# CFA_T_4L.net
KiCad netlist of a schematic drawn in EAGLE
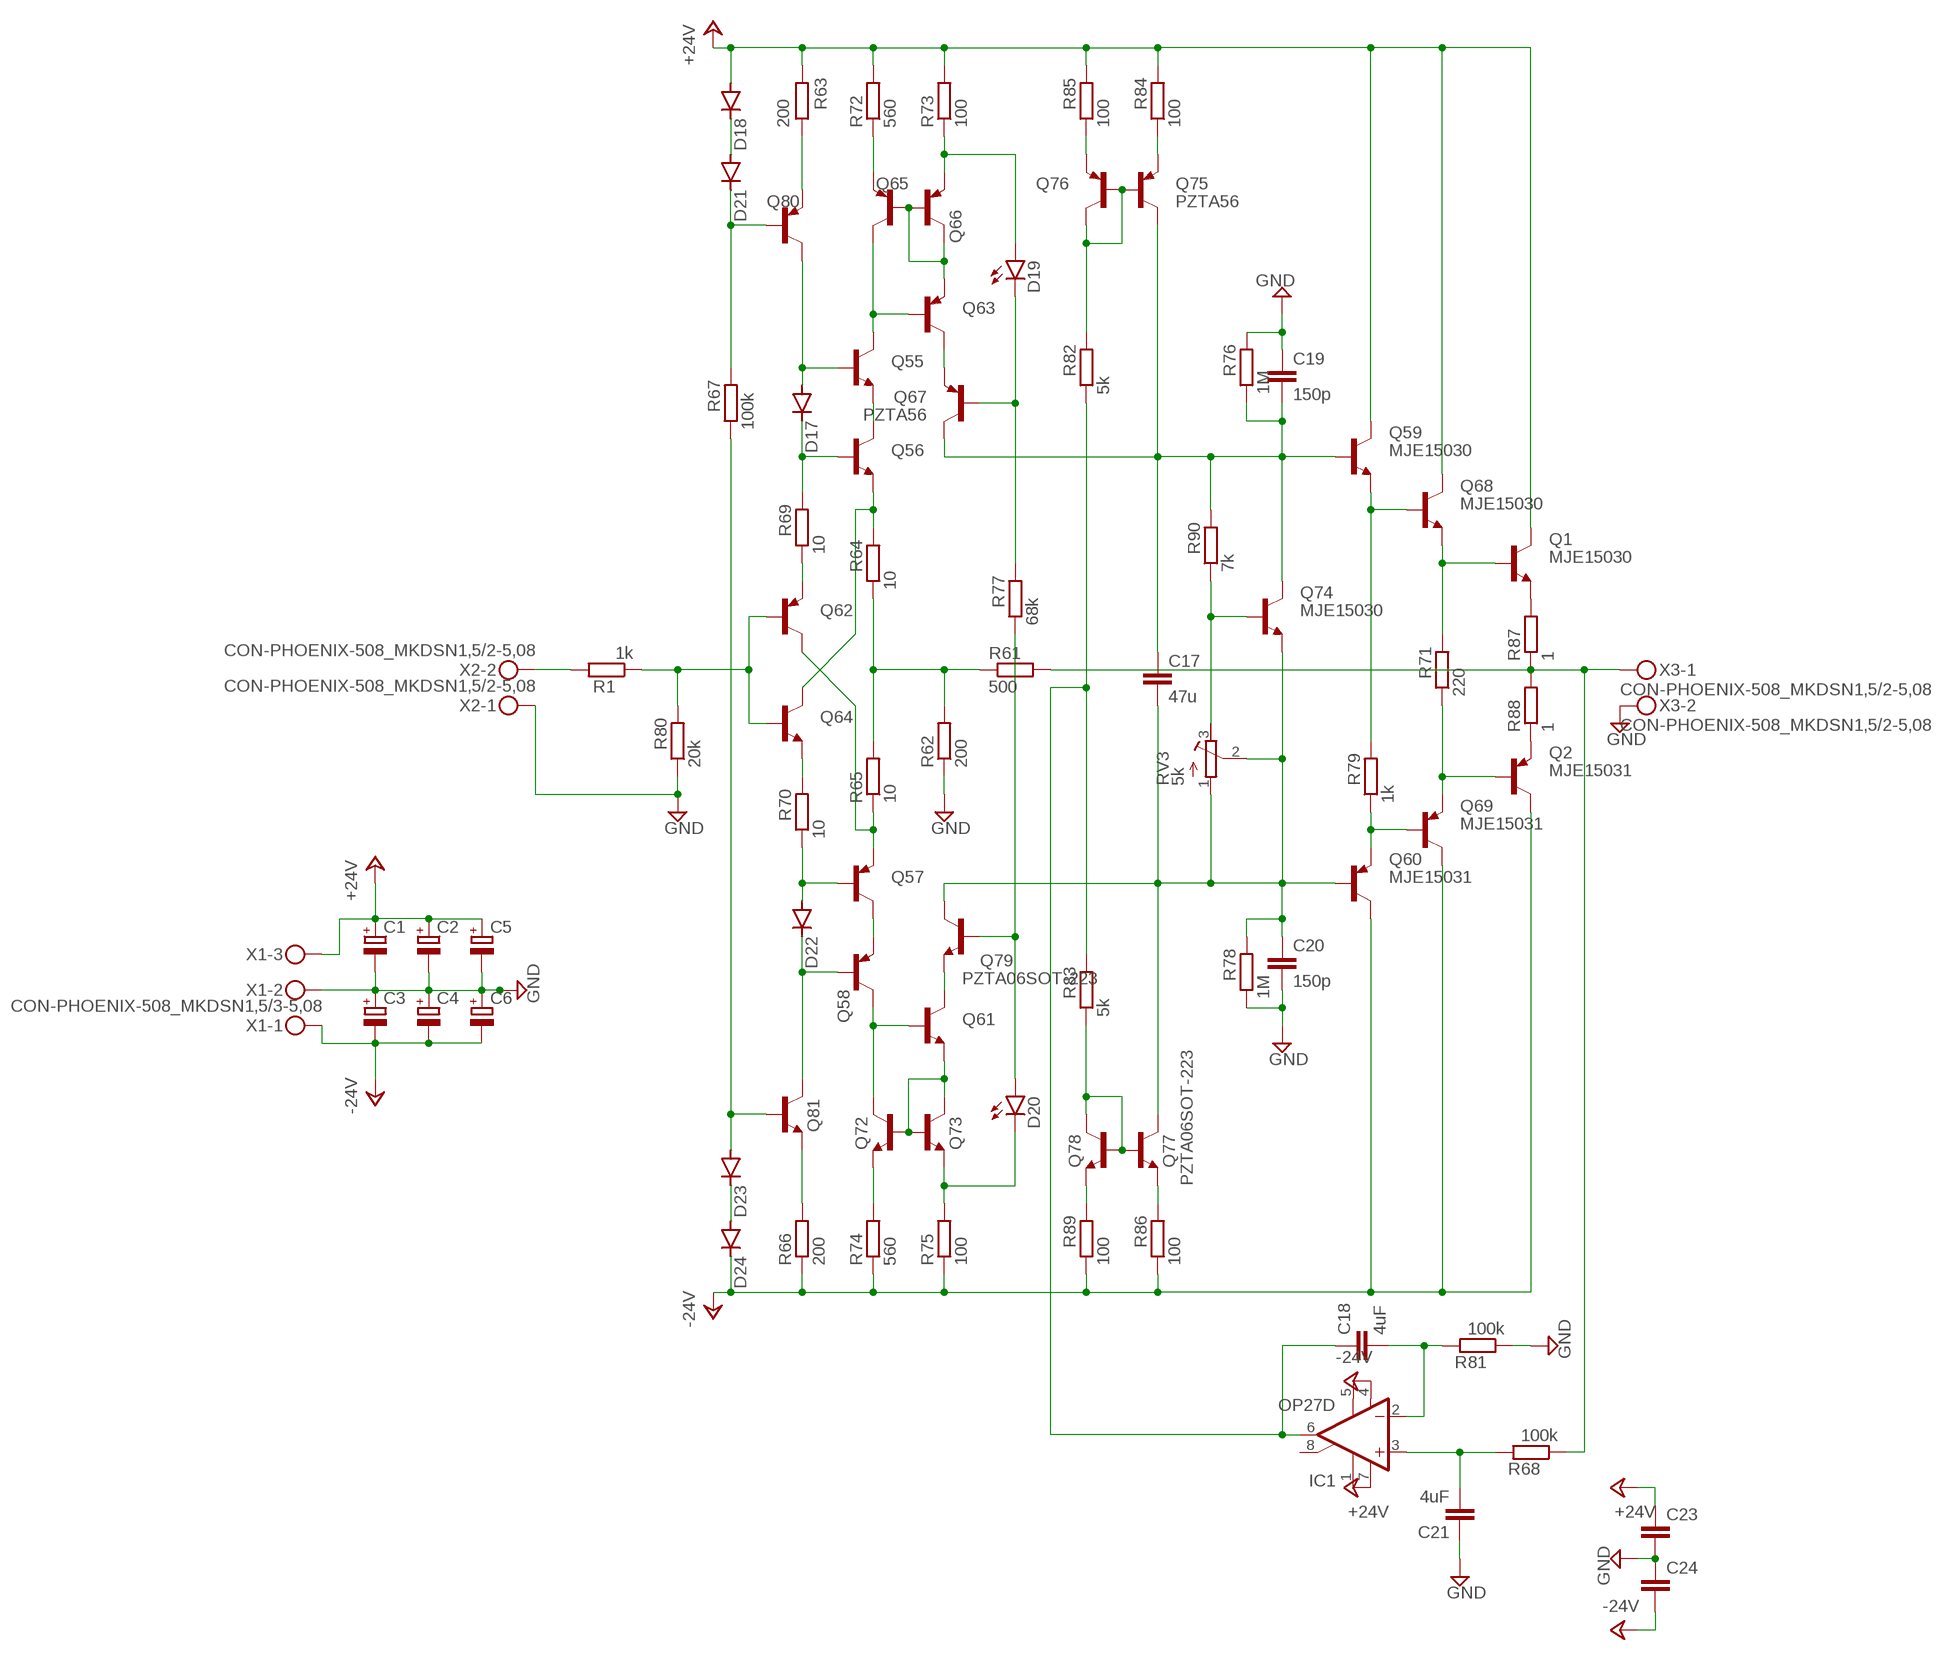
[diagram p0: schematic, sheet 1]

(export (version "E")
  (design (tool "Eeschema 10.0.6"))
  (components
    (comp (ref "C1")
      (value "CPOL-EUE3.5-8")
      (footprint "eagle-import:E3,5-8")
      (libsource (lib "eagle-import") (part "CPOL-EUE3.5-8"))
    )
    (comp (ref "C2")
      (value "CPOL-EUE3.5-8")
      (footprint "eagle-import:E3,5-8")
      (libsource (lib "eagle-import") (part "CPOL-EUE3.5-8"))
    )
    (comp (ref "C3")
      (value "CPOL-EUE3.5-8")
      (footprint "eagle-import:E3,5-8")
      (libsource (lib "eagle-import") (part "CPOL-EUE3.5-8"))
    )
    (comp (ref "C4")
      (value "CPOL-EUE3.5-8")
      (footprint "eagle-import:E3,5-8")
      (libsource (lib "eagle-import") (part "CPOL-EUE3.5-8"))
    )
    (comp (ref "C5")
      (value "CPOL-EUE3.5-8")
      (footprint "eagle-import:E3,5-8")
      (libsource (lib "eagle-import") (part "CPOL-EUE3.5-8"))
    )
    (comp (ref "C6")
      (value "CPOL-EUE3.5-8")
      (footprint "eagle-import:E3,5-8")
      (libsource (lib "eagle-import") (part "CPOL-EUE3.5-8"))
    )
    (comp (ref "C17")
      (value "47u")
      (footprint "eagle-import:C1210")
      (fields (field (name "SPICEPREFIX") "C"))
      (libsource (lib "eagle-import") (part "C-EUC1210"))
    )
    (comp (ref "C18")
      (value "4uF")
      (footprint "eagle-import:C1210")
      (fields (field (name "SPICEPREFIX") "C"))
      (libsource (lib "eagle-import") (part "C-EUC1210"))
    )
    (comp (ref "C19")
      (value "150p")
      (footprint "eagle-import:C0805")
      (fields (field (name "SPICEPREFIX") "C"))
      (libsource (lib "eagle-import") (part "C-EUC0805"))
    )
    (comp (ref "C20")
      (value "150p")
      (footprint "eagle-import:C0805")
      (fields (field (name "SPICEPREFIX") "C"))
      (libsource (lib "eagle-import") (part "C-EUC0805"))
    )
    (comp (ref "C21")
      (value "4uF")
      (footprint "eagle-import:C1210")
      (fields (field (name "SPICEPREFIX") "C"))
      (libsource (lib "eagle-import") (part "C-EUC1210"))
    )
    (comp (ref "C23")
      (value "C-EUC0603K")
      (footprint "eagle-import:C0603K")
      (libsource (lib "eagle-import") (part "C-EUC0603K"))
    )
    (comp (ref "C24")
      (value "C-EUC0603K")
      (footprint "eagle-import:C0603K")
      (libsource (lib "eagle-import") (part "C-EUC0603K"))
    )
    (comp (ref "D17")
      (value "DIODE-SOD80C")
      (footprint "eagle-import:SOD80C")
      (fields (field (name "SPICEPREFIX") "D"))
      (libsource (lib "eagle-import") (part "DIODE-SOD80C"))
    )
    (comp (ref "D18")
      (value "DIODE-SOD80C")
      (footprint "eagle-import:SOD80C")
      (fields (field (name "SPICEPREFIX") "D"))
      (libsource (lib "eagle-import") (part "DIODE-SOD80C"))
    )
    (comp (ref "D19")
      (value "LED3MM")
      (footprint "eagle-import:LED3MM")
      (fields (field (name "SPICEPREFIX") "D"))
      (libsource (lib "eagle-import") (part "LED3MM"))
    )
    (comp (ref "D20")
      (value "LED3MM")
      (footprint "eagle-import:LED3MM")
      (fields (field (name "SPICEPREFIX") "D"))
      (libsource (lib "eagle-import") (part "LED3MM"))
    )
    (comp (ref "D21")
      (value "DIODE-SOD80C")
      (footprint "eagle-import:SOD80C")
      (fields (field (name "SPICEPREFIX") "D"))
      (libsource (lib "eagle-import") (part "DIODE-SOD80C"))
    )
    (comp (ref "D22")
      (value "DIODE-SOD80C")
      (footprint "eagle-import:SOD80C")
      (fields (field (name "SPICEPREFIX") "D"))
      (libsource (lib "eagle-import") (part "DIODE-SOD80C"))
    )
    (comp (ref "D23")
      (value "DIODE-SOD80C")
      (footprint "eagle-import:SOD80C")
      (fields (field (name "SPICEPREFIX") "D"))
      (libsource (lib "eagle-import") (part "DIODE-SOD80C"))
    )
    (comp (ref "D24")
      (value "DIODE-SOD80C")
      (footprint "eagle-import:SOD80C")
      (fields (field (name "SPICEPREFIX") "D"))
      (libsource (lib "eagle-import") (part "DIODE-SOD80C"))
    )
    (comp (ref "IC1")
      (value "OP27D")
      (footprint "eagle-import:SO08")
      (libsource (lib "eagle-import") (part "OP27D"))
    )
    (comp (ref "Q1")
      (value "MJE15030")
      (footprint "eagle-import:TRANSISTOR_TO220KG")
      (fields (field (name "SPICEPREFIX") "Q"))
      (libsource (lib "eagle-import") (part "TRANSISTOR_MJE15030"))
    )
    (comp (ref "Q2")
      (value "MJE15031")
      (footprint "eagle-import:TRANSISTOR_TO220KG")
      (fields (field (name "SPICEPREFIX") "Q"))
      (libsource (lib "eagle-import") (part "TRANSISTOR_MJE15031"))
    )
    (comp (ref "Q55")
      (value "TRANSISTOR_BC850-NPN-SOT23-BEC")
      (footprint "eagle-import:TRANSISTOR_SOT23-BEC")
      (fields (field (name "SPICEPREFIX") "Q"))
      (libsource (lib "eagle-import") (part "TRANSISTOR_-NPN-SOT23-BECBC850"))
    )
    (comp (ref "Q56")
      (value "TRANSISTOR_BC850-NPN-SOT23-BEC")
      (footprint "eagle-import:TRANSISTOR_SOT23-BEC")
      (fields (field (name "SPICEPREFIX") "Q"))
      (libsource (lib "eagle-import") (part "TRANSISTOR_-NPN-SOT23-BECBC850"))
    )
    (comp (ref "Q57")
      (value "TRANSISTOR_BC857C-PNP-SOT23-BEC")
      (footprint "eagle-import:TRANSISTOR_SOT23-BEC")
      (fields (field (name "SPICEPREFIX") "Q"))
      (libsource (lib "eagle-import") (part "TRANSISTOR_-PNP-SOT23-BECBC857C"))
    )
    (comp (ref "Q58")
      (value "TRANSISTOR_BC857C-PNP-SOT23-BEC")
      (footprint "eagle-import:TRANSISTOR_SOT23-BEC")
      (fields (field (name "SPICEPREFIX") "Q"))
      (libsource (lib "eagle-import") (part "TRANSISTOR_-PNP-SOT23-BECBC857C"))
    )
    (comp (ref "Q59")
      (value "MJE15030")
      (footprint "eagle-import:TRANSISTOR_TO220KG")
      (fields (field (name "SPICEPREFIX") "Q"))
      (libsource (lib "eagle-import") (part "TRANSISTOR_MJE15030"))
    )
    (comp (ref "Q60")
      (value "MJE15031")
      (footprint "eagle-import:TRANSISTOR_TO220KG")
      (fields (field (name "SPICEPREFIX") "Q"))
      (libsource (lib "eagle-import") (part "TRANSISTOR_MJE15031"))
    )
    (comp (ref "Q61")
      (value "TRANSISTOR_BC847-NPN-SOT23-BEC")
      (footprint "eagle-import:TRANSISTOR_SOT23-BEC")
      (fields (field (name "SPICEPREFIX") "Q"))
      (libsource (lib "eagle-import") (part "TRANSISTOR_-NPN-SOT23-BECBC847"))
    )
    (comp (ref "Q62")
      (value "TRANSISTOR_BC857C-PNP-SOT23-BEC")
      (footprint "eagle-import:TRANSISTOR_SOT23-BEC")
      (fields (field (name "SPICEPREFIX") "Q"))
      (libsource (lib "eagle-import") (part "TRANSISTOR_-PNP-SOT23-BECBC857C"))
    )
    (comp (ref "Q63")
      (value "TRANSISTOR_BC857C-PNP-SOT23-BEC")
      (footprint "eagle-import:TRANSISTOR_SOT23-BEC")
      (fields (field (name "SPICEPREFIX") "Q"))
      (libsource (lib "eagle-import") (part "TRANSISTOR_-PNP-SOT23-BECBC857C"))
    )
    (comp (ref "Q64")
      (value "TRANSISTOR_BC850-NPN-SOT23-BEC")
      (footprint "eagle-import:TRANSISTOR_SOT23-BEC")
      (fields (field (name "SPICEPREFIX") "Q"))
      (libsource (lib "eagle-import") (part "TRANSISTOR_-NPN-SOT23-BECBC850"))
    )
    (comp (ref "Q65")
      (value "TRANSISTOR_BC857C-PNP-SOT23-BEC")
      (footprint "eagle-import:TRANSISTOR_SOT23-BEC")
      (fields (field (name "SPICEPREFIX") "Q"))
      (libsource (lib "eagle-import") (part "TRANSISTOR_-PNP-SOT23-BECBC857C"))
    )
    (comp (ref "Q66")
      (value "TRANSISTOR_BC857C-PNP-SOT23-BEC")
      (footprint "eagle-import:TRANSISTOR_SOT23-BEC")
      (fields (field (name "SPICEPREFIX") "Q"))
      (libsource (lib "eagle-import") (part "TRANSISTOR_-PNP-SOT23-BECBC857C"))
    )
    (comp (ref "Q67")
      (value "PZTA56")
      (footprint "eagle-import:SOT223")
      (fields (field (name "SPICEPREFIX") "Q"))
      (libsource (lib "eagle-import") (part "PZTA56"))
    )
    (comp (ref "Q68")
      (value "MJE15030")
      (footprint "eagle-import:TRANSISTOR_TO220KG")
      (fields (field (name "SPICEPREFIX") "Q"))
      (libsource (lib "eagle-import") (part "TRANSISTOR_MJE15030"))
    )
    (comp (ref "Q69")
      (value "MJE15031")
      (footprint "eagle-import:TRANSISTOR_TO220KG")
      (fields (field (name "SPICEPREFIX") "Q"))
      (libsource (lib "eagle-import") (part "TRANSISTOR_MJE15031"))
    )
    (comp (ref "Q72")
      (value "TRANSISTOR_BC850-NPN-SOT23-BEC")
      (footprint "eagle-import:TRANSISTOR_SOT23-BEC")
      (fields (field (name "SPICEPREFIX") "Q"))
      (libsource (lib "eagle-import") (part "TRANSISTOR_-NPN-SOT23-BECBC850"))
    )
    (comp (ref "Q73")
      (value "TRANSISTOR_BC850-NPN-SOT23-BEC")
      (footprint "eagle-import:TRANSISTOR_SOT23-BEC")
      (fields (field (name "SPICEPREFIX") "Q"))
      (libsource (lib "eagle-import") (part "TRANSISTOR_-NPN-SOT23-BECBC850"))
    )
    (comp (ref "Q74")
      (value "MJE15030")
      (footprint "eagle-import:TRANSISTOR_TO220KG")
      (fields (field (name "SPICEPREFIX") "Q"))
      (libsource (lib "eagle-import") (part "TRANSISTOR_MJE15030"))
    )
    (comp (ref "Q75")
      (value "PZTA56")
      (footprint "eagle-import:SOT223")
      (fields (field (name "SPICEPREFIX") "Q"))
      (libsource (lib "eagle-import") (part "PZTA56"))
    )
    (comp (ref "Q76")
      (value "TRANSISTOR_BC857C-PNP-SOT23-BEC")
      (footprint "eagle-import:TRANSISTOR_SOT23-BEC")
      (fields (field (name "SPICEPREFIX") "Q"))
      (libsource (lib "eagle-import") (part "TRANSISTOR_-PNP-SOT23-BECBC857C"))
    )
    (comp (ref "Q77")
      (value "PZTA06SOT-223")
      (footprint "eagle-import:SOT223")
      (fields (field (name "SPICEPREFIX") "Q"))
      (libsource (lib "eagle-import") (part "PZTA06SOT-223"))
    )
    (comp (ref "Q78")
      (value "TRANSISTOR_BC850-NPN-SOT23-BEC")
      (footprint "eagle-import:TRANSISTOR_SOT23-BEC")
      (fields (field (name "SPICEPREFIX") "Q"))
      (libsource (lib "eagle-import") (part "TRANSISTOR_-NPN-SOT23-BECBC850"))
    )
    (comp (ref "Q79")
      (value "PZTA06SOT-223")
      (footprint "eagle-import:SOT223")
      (fields (field (name "SPICEPREFIX") "Q"))
      (libsource (lib "eagle-import") (part "PZTA06SOT-223"))
    )
    (comp (ref "Q80")
      (value "TRANSISTOR_BC857C-PNP-SOT23-BEC")
      (footprint "eagle-import:TRANSISTOR_SOT23-BEC")
      (fields (field (name "SPICEPREFIX") "Q"))
      (libsource (lib "eagle-import") (part "TRANSISTOR_-PNP-SOT23-BECBC857C"))
    )
    (comp (ref "Q81")
      (value "TRANSISTOR_BC850-NPN-SOT23-BEC")
      (footprint "eagle-import:TRANSISTOR_SOT23-BEC")
      (fields (field (name "SPICEPREFIX") "Q"))
      (libsource (lib "eagle-import") (part "TRANSISTOR_-NPN-SOT23-BECBC850"))
    )
    (comp (ref "R1")
      (value "1k")
      (footprint "eagle-import:MINI_MELF-0204W")
      (fields (field (name "SPICEPREFIX") "R"))
      (libsource (lib "eagle-import") (part "R-EU_MELF0204W"))
    )
    (comp (ref "R61")
      (value "500")
      (footprint "eagle-import:MINI_MELF-0204W")
      (fields (field (name "SPICEPREFIX") "R"))
      (libsource (lib "eagle-import") (part "R-EU_MELF0204W"))
    )
    (comp (ref "R62")
      (value "200")
      (footprint "eagle-import:MINI_MELF-0204W")
      (fields (field (name "SPICEPREFIX") "R"))
      (libsource (lib "eagle-import") (part "R-EU_MELF0204W"))
    )
    (comp (ref "R63")
      (value "200")
      (footprint "eagle-import:MINI_MELF-0204W")
      (fields (field (name "SPICEPREFIX") "R"))
      (libsource (lib "eagle-import") (part "R-EU_MELF0204W"))
    )
    (comp (ref "R64")
      (value "10")
      (footprint "eagle-import:MINI_MELF-0204W")
      (fields (field (name "SPICEPREFIX") "R"))
      (libsource (lib "eagle-import") (part "R-EU_MELF0204W"))
    )
    (comp (ref "R65")
      (value "10")
      (footprint "eagle-import:MINI_MELF-0204W")
      (fields (field (name "SPICEPREFIX") "R"))
      (libsource (lib "eagle-import") (part "R-EU_MELF0204W"))
    )
    (comp (ref "R66")
      (value "200")
      (footprint "eagle-import:MINI_MELF-0204W")
      (fields (field (name "SPICEPREFIX") "R"))
      (libsource (lib "eagle-import") (part "R-EU_MELF0204W"))
    )
    (comp (ref "R67")
      (value "100k")
      (footprint "eagle-import:MINI_MELF-0204W")
      (fields (field (name "SPICEPREFIX") "R"))
      (libsource (lib "eagle-import") (part "R-EU_MELF0204W"))
    )
    (comp (ref "R68")
      (value "100k")
      (footprint "eagle-import:MINI_MELF-0204W")
      (fields (field (name "SPICEPREFIX") "R"))
      (libsource (lib "eagle-import") (part "R-EU_MELF0204W"))
    )
    (comp (ref "R69")
      (value "10")
      (footprint "eagle-import:MINI_MELF-0204W")
      (fields (field (name "SPICEPREFIX") "R"))
      (libsource (lib "eagle-import") (part "R-EU_MELF0204W"))
    )
    (comp (ref "R70")
      (value "10")
      (footprint "eagle-import:MINI_MELF-0204W")
      (fields (field (name "SPICEPREFIX") "R"))
      (libsource (lib "eagle-import") (part "R-EU_MELF0204W"))
    )
    (comp (ref "R71")
      (value "220")
      (footprint "eagle-import:MINI_MELF-0204W")
      (fields (field (name "SPICEPREFIX") "R"))
      (libsource (lib "eagle-import") (part "R-EU_MELF0204W"))
    )
    (comp (ref "R72")
      (value "560")
      (footprint "eagle-import:MINI_MELF-0204W")
      (fields (field (name "SPICEPREFIX") "R"))
      (libsource (lib "eagle-import") (part "R-EU_MELF0204W"))
    )
    (comp (ref "R73")
      (value "100")
      (footprint "eagle-import:MINI_MELF-0204W")
      (fields (field (name "SPICEPREFIX") "R"))
      (libsource (lib "eagle-import") (part "R-EU_MELF0204W"))
    )
    (comp (ref "R74")
      (value "560")
      (footprint "eagle-import:MINI_MELF-0204W")
      (fields (field (name "SPICEPREFIX") "R"))
      (libsource (lib "eagle-import") (part "R-EU_MELF0204W"))
    )
    (comp (ref "R75")
      (value "100")
      (footprint "eagle-import:MINI_MELF-0204W")
      (fields (field (name "SPICEPREFIX") "R"))
      (libsource (lib "eagle-import") (part "R-EU_MELF0204W"))
    )
    (comp (ref "R76")
      (value "1M")
      (footprint "eagle-import:MINI_MELF-0204W")
      (fields (field (name "SPICEPREFIX") "R"))
      (libsource (lib "eagle-import") (part "R-EU_MELF0204W"))
    )
    (comp (ref "R77")
      (value "68k")
      (footprint "eagle-import:MINI_MELF-0204W")
      (fields (field (name "SPICEPREFIX") "R"))
      (libsource (lib "eagle-import") (part "R-EU_MELF0204W"))
    )
    (comp (ref "R78")
      (value "1M")
      (footprint "eagle-import:MINI_MELF-0204W")
      (fields (field (name "SPICEPREFIX") "R"))
      (libsource (lib "eagle-import") (part "R-EU_MELF0204W"))
    )
    (comp (ref "R79")
      (value "1k")
      (footprint "eagle-import:MINI_MELF-0204W")
      (fields (field (name "SPICEPREFIX") "R"))
      (libsource (lib "eagle-import") (part "R-EU_MELF0204W"))
    )
    (comp (ref "R80")
      (value "20k")
      (footprint "eagle-import:MINI_MELF-0204W")
      (fields (field (name "SPICEPREFIX") "R"))
      (libsource (lib "eagle-import") (part "R-EU_MELF0204W"))
    )
    (comp (ref "R81")
      (value "100k")
      (footprint "eagle-import:MINI_MELF-0204W")
      (fields (field (name "SPICEPREFIX") "R"))
      (libsource (lib "eagle-import") (part "R-EU_MELF0204W"))
    )
    (comp (ref "R82")
      (value "5k")
      (footprint "eagle-import:MINI_MELF-0204W")
      (fields (field (name "SPICEPREFIX") "R"))
      (libsource (lib "eagle-import") (part "R-EU_MELF0204W"))
    )
    (comp (ref "R83")
      (value "5k")
      (footprint "eagle-import:MINI_MELF-0204W")
      (fields (field (name "SPICEPREFIX") "R"))
      (libsource (lib "eagle-import") (part "R-EU_MELF0204W"))
    )
    (comp (ref "R84")
      (value "100")
      (footprint "eagle-import:MINI_MELF-0204W")
      (fields (field (name "SPICEPREFIX") "R"))
      (libsource (lib "eagle-import") (part "R-EU_MELF0204W"))
    )
    (comp (ref "R85")
      (value "100")
      (footprint "eagle-import:MINI_MELF-0204W")
      (fields (field (name "SPICEPREFIX") "R"))
      (libsource (lib "eagle-import") (part "R-EU_MELF0204W"))
    )
    (comp (ref "R86")
      (value "100")
      (footprint "eagle-import:MINI_MELF-0204W")
      (fields (field (name "SPICEPREFIX") "R"))
      (libsource (lib "eagle-import") (part "R-EU_MELF0204W"))
    )
    (comp (ref "R87")
      (value "1")
      (footprint "eagle-import:TO220-2")
      (fields (field (name "SPICEPREFIX") "R"))
      (libsource (lib "eagle-import") (part "R-EU_TO220"))
    )
    (comp (ref "R88")
      (value "1")
      (footprint "eagle-import:TO220-2")
      (fields (field (name "SPICEPREFIX") "R"))
      (libsource (lib "eagle-import") (part "R-EU_TO220"))
    )
    (comp (ref "R89")
      (value "100")
      (footprint "eagle-import:MINI_MELF-0204W")
      (fields (field (name "SPICEPREFIX") "R"))
      (libsource (lib "eagle-import") (part "R-EU_MELF0204W"))
    )
    (comp (ref "R90")
      (value "7k")
      (footprint "eagle-import:MINI_MELF-0204W")
      (fields (field (name "SPICEPREFIX") "R"))
      (libsource (lib "eagle-import") (part "R-EU_MELF0204W"))
    )
    (comp (ref "RV3")
      (value "5k")
      (footprint "eagle-import:RTRIM3296W")
      (fields (field (name "SPICEPREFIX") "Z"))
      (libsource (lib "eagle-import") (part "R-TRIMM3296W"))
    )
    (comp (ref "X1")
      (value "CON-PHOENIX-508_MKDSN1,5/3-5,08")
      (footprint "eagle-import:CON-PHOENIX-508_MKDSN1,5_3-5,08")
      (libsource (lib "eagle-import") (part "CON-PHOENIX-508_MKDSN1,5/3-5,08"))
    )
    (comp (ref "X2")
      (value "CON-PHOENIX-508_MKDSN1,5/2-5,08")
      (footprint "eagle-import:CON-PHOENIX-508_MKDSN1,5_2-5,08")
      (libsource (lib "eagle-import") (part "CON-PHOENIX-508_MKDSN1,5/2-5,08"))
    )
    (comp (ref "X3")
      (value "CON-PHOENIX-508_MKDSN1,5/2-5,08")
      (footprint "eagle-import:CON-PHOENIX-508_MKDSN1,5_2-5,08")
      (libsource (lib "eagle-import") (part "CON-PHOENIX-508_MKDSN1,5/2-5,08"))
    )
  )
  (nets
    (net (code "1") (name "+24V") (class "Default")
      (node (ref "C1") (pin "+") (pinfunction "+_+") (pintype "passive"))
      (node (ref "C2") (pin "+") (pinfunction "+_+") (pintype "passive"))
      (node (ref "C23") (pin "1") (pinfunction "1_1") (pintype "passive"))
      (node (ref "C5") (pin "+") (pinfunction "+_+") (pintype "passive"))
      (node (ref "D18") (pin "A") (pinfunction "A_A") (pintype "passive"))
      (node (ref "IC1") (pin "7") (pinfunction "V+_7") (pintype "power_in"))
      (node (ref "Q1") (pin "2") (pinfunction "C_2") (pintype "passive"))
      (node (ref "Q59") (pin "2") (pinfunction "C_2") (pintype "passive"))
      (node (ref "Q68") (pin "2") (pinfunction "C_2") (pintype "passive"))
      (node (ref "R63") (pin "2") (pinfunction "2_2") (pintype "passive"))
      (node (ref "R72") (pin "2") (pinfunction "2_2") (pintype "passive"))
      (node (ref "R73") (pin "2") (pinfunction "2_2") (pintype "passive"))
      (node (ref "R84") (pin "2") (pinfunction "2_2") (pintype "passive"))
      (node (ref "R85") (pin "2") (pinfunction "2_2") (pintype "passive"))
      (node (ref "X1") (pin "3") (pinfunction "KL_3") (pintype "passive"))
    )
    (net (code "2") (name "-24V") (class "Default")
      (node (ref "C24") (pin "2") (pinfunction "2_2") (pintype "passive"))
      (node (ref "C3") (pin "-") (pinfunction "-_-") (pintype "passive"))
      (node (ref "C4") (pin "-") (pinfunction "-_-") (pintype "passive"))
      (node (ref "C6") (pin "-") (pinfunction "-_-") (pintype "passive"))
      (node (ref "D24") (pin "C") (pinfunction "C_C") (pintype "passive"))
      (node (ref "IC1") (pin "4") (pinfunction "V-_4") (pintype "power_in"))
      (node (ref "Q2") (pin "2") (pinfunction "C_2") (pintype "passive"))
      (node (ref "Q60") (pin "2") (pinfunction "C_2") (pintype "passive"))
      (node (ref "Q69") (pin "2") (pinfunction "C_2") (pintype "passive"))
      (node (ref "R66") (pin "1") (pinfunction "1_1") (pintype "passive"))
      (node (ref "R74") (pin "1") (pinfunction "1_1") (pintype "passive"))
      (node (ref "R75") (pin "1") (pinfunction "1_1") (pintype "passive"))
      (node (ref "R86") (pin "1") (pinfunction "1_1") (pintype "passive"))
      (node (ref "R89") (pin "1") (pinfunction "1_1") (pintype "passive"))
      (node (ref "X1") (pin "1") (pinfunction "KL_1") (pintype "passive"))
    )
    (net (code "3") (name "GND") (class "Default")
      (node (ref "C1") (pin "-") (pinfunction "-_-") (pintype "passive"))
      (node (ref "C19") (pin "1") (pinfunction "1_1") (pintype "passive"))
      (node (ref "C2") (pin "-") (pinfunction "-_-") (pintype "passive"))
      (node (ref "C20") (pin "2") (pinfunction "2_2") (pintype "passive"))
      (node (ref "C21") (pin "1") (pinfunction "1_1") (pintype "passive"))
      (node (ref "C23") (pin "2") (pinfunction "2_2") (pintype "passive"))
      (node (ref "C24") (pin "1") (pinfunction "1_1") (pintype "passive"))
      (node (ref "C3") (pin "+") (pinfunction "+_+") (pintype "passive"))
      (node (ref "C4") (pin "+") (pinfunction "+_+") (pintype "passive"))
      (node (ref "C5") (pin "-") (pinfunction "-_-") (pintype "passive"))
      (node (ref "C6") (pin "+") (pinfunction "+_+") (pintype "passive"))
      (node (ref "R62") (pin "1") (pinfunction "1_1") (pintype "passive"))
      (node (ref "R76") (pin "2") (pinfunction "2_2") (pintype "passive"))
      (node (ref "R78") (pin "1") (pinfunction "1_1") (pintype "passive"))
      (node (ref "R80") (pin "1") (pinfunction "1_1") (pintype "passive"))
      (node (ref "R81") (pin "1") (pinfunction "1_1") (pintype "passive"))
      (node (ref "X1") (pin "2") (pinfunction "KL_2") (pintype "passive"))
      (node (ref "X2") (pin "1") (pinfunction "KL_1") (pintype "passive"))
      (node (ref "X3") (pin "2") (pinfunction "KL_2") (pintype "passive"))
    )
    (net (code "4") (name "Net-(D17-PadA)") (class "Default")
      (node (ref "D17") (pin "A") (pinfunction "A_A") (pintype "passive"))
      (node (ref "Q55") (pin "B") (pinfunction "B_B") (pintype "passive"))
      (node (ref "Q80") (pin "C") (pinfunction "C_C") (pintype "passive"))
    )
    (net (code "5") (name "Net-(D17-PadC)") (class "Default")
      (node (ref "D17") (pin "C") (pinfunction "C_C") (pintype "passive"))
      (node (ref "Q56") (pin "B") (pinfunction "B_B") (pintype "passive"))
      (node (ref "R69") (pin "2") (pinfunction "2_2") (pintype "passive"))
    )
    (net (code "6") (name "Net-(D18-PadC)") (class "Default")
      (node (ref "D18") (pin "C") (pinfunction "C_C") (pintype "passive"))
      (node (ref "D21") (pin "A") (pinfunction "A_A") (pintype "passive"))
    )
    (net (code "7") (name "Net-(D19-C)") (class "Default")
      (node (ref "D19") (pin "K") (pinfunction "C_K") (pintype "passive"))
      (node (ref "Q67") (pin "1") (pinfunction "B_1") (pintype "passive"))
      (node (ref "R77") (pin "2") (pinfunction "2_2") (pintype "passive"))
    )
    (net (code "8") (name "Net-(D19-PadA)") (class "Default")
      (node (ref "D19") (pin "A") (pinfunction "A_A") (pintype "passive"))
      (node (ref "Q66") (pin "E") (pinfunction "E_E") (pintype "passive"))
      (node (ref "R73") (pin "1") (pinfunction "1_1") (pintype "passive"))
    )
    (net (code "9") (name "Net-(D20-C)") (class "Default")
      (node (ref "D20") (pin "K") (pinfunction "C_K") (pintype "passive"))
      (node (ref "Q73") (pin "E") (pinfunction "E_E") (pintype "passive"))
      (node (ref "R75") (pin "2") (pinfunction "2_2") (pintype "passive"))
    )
    (net (code "10") (name "Net-(D21-PadC)") (class "Default")
      (node (ref "D21") (pin "C") (pinfunction "C_C") (pintype "passive"))
      (node (ref "Q80") (pin "B") (pinfunction "B_B") (pintype "passive"))
      (node (ref "R67") (pin "2") (pinfunction "2_2") (pintype "passive"))
    )
    (net (code "11") (name "Net-(D22-PadA)") (class "Default")
      (node (ref "D22") (pin "A") (pinfunction "A_A") (pintype "passive"))
      (node (ref "Q57") (pin "B") (pinfunction "B_B") (pintype "passive"))
      (node (ref "R70") (pin "1") (pinfunction "1_1") (pintype "passive"))
    )
    (net (code "12") (name "Net-(D22-PadC)") (class "Default")
      (node (ref "D22") (pin "C") (pinfunction "C_C") (pintype "passive"))
      (node (ref "Q58") (pin "B") (pinfunction "B_B") (pintype "passive"))
      (node (ref "Q81") (pin "C") (pinfunction "C_C") (pintype "passive"))
    )
    (net (code "13") (name "Net-(D23-PadA)") (class "Default")
      (node (ref "D23") (pin "A") (pinfunction "A_A") (pintype "passive"))
      (node (ref "Q81") (pin "B") (pinfunction "B_B") (pintype "passive"))
      (node (ref "R67") (pin "1") (pinfunction "1_1") (pintype "passive"))
    )
    (net (code "14") (name "Net-(D23-PadC)") (class "Default")
      (node (ref "D23") (pin "C") (pinfunction "C_C") (pintype "passive"))
      (node (ref "D24") (pin "A") (pinfunction "A_A") (pintype "passive"))
    )
    (net (code "15") (name "Net-(IC1-+IN)") (class "Default")
      (node (ref "C21") (pin "2") (pinfunction "2_2") (pintype "passive"))
      (node (ref "IC1") (pin "3") (pinfunction "+IN_3") (pintype "input"))
      (node (ref "R68") (pin "2") (pinfunction "2_2") (pintype "passive"))
    )
    (net (code "16") (name "Net-(IC1--IN)") (class "Default")
      (node (ref "C18") (pin "2") (pinfunction "2_2") (pintype "passive"))
      (node (ref "IC1") (pin "2") (pinfunction "-IN_2") (pintype "input"))
      (node (ref "R81") (pin "2") (pinfunction "2_2") (pintype "passive"))
    )
    (net (code "17") (name "Net-(IC1-OUT)") (class "Default")
      (node (ref "C18") (pin "1") (pinfunction "1_1") (pintype "passive"))
      (node (ref "IC1") (pin "6") (pinfunction "OUT_6") (pintype "output"))
      (node (ref "R82") (pin "1") (pinfunction "1_1") (pintype "passive"))
      (node (ref "R83") (pin "2") (pinfunction "2_2") (pintype "passive"))
    )
    (net (code "18") (name "Net-(Q1-B)") (class "Default")
      (node (ref "Q1") (pin "1") (pinfunction "B_1") (pintype "passive"))
      (node (ref "Q68") (pin "3") (pinfunction "E_3") (pintype "passive"))
      (node (ref "R71") (pin "2") (pinfunction "2_2") (pintype "passive"))
    )
    (net (code "19") (name "Net-(Q1-E)") (class "Default")
      (node (ref "Q1") (pin "3") (pinfunction "E_3") (pintype "passive"))
      (node (ref "R87") (pin "2") (pinfunction "2_2") (pintype "passive"))
    )
    (net (code "20") (name "Net-(Q2-B)") (class "Default")
      (node (ref "Q2") (pin "1") (pinfunction "B_1") (pintype "passive"))
      (node (ref "Q69") (pin "3") (pinfunction "E_3") (pintype "passive"))
      (node (ref "R71") (pin "1") (pinfunction "1_1") (pintype "passive"))
    )
    (net (code "21") (name "Net-(Q2-E)") (class "Default")
      (node (ref "Q2") (pin "3") (pinfunction "E_3") (pintype "passive"))
      (node (ref "R88") (pin "1") (pinfunction "1_1") (pintype "passive"))
    )
    (net (code "22") (name "Net-(Q55-PadC)") (class "Default")
      (node (ref "Q55") (pin "C") (pinfunction "C_C") (pintype "passive"))
      (node (ref "Q63") (pin "B") (pinfunction "B_B") (pintype "passive"))
      (node (ref "Q65") (pin "C") (pinfunction "C_C") (pintype "passive"))
    )
    (net (code "23") (name "Net-(Q55-PadE)") (class "Default")
      (node (ref "Q55") (pin "E") (pinfunction "E_E") (pintype "passive"))
      (node (ref "Q56") (pin "C") (pinfunction "C_C") (pintype "passive"))
    )
    (net (code "24") (name "Net-(Q56-PadE)") (class "Default")
      (node (ref "Q56") (pin "E") (pinfunction "E_E") (pintype "passive"))
      (node (ref "Q64") (pin "C") (pinfunction "C_C") (pintype "passive"))
      (node (ref "R64") (pin "2") (pinfunction "2_2") (pintype "passive"))
    )
    (net (code "25") (name "Net-(Q57-PadC)") (class "Default")
      (node (ref "Q57") (pin "C") (pinfunction "C_C") (pintype "passive"))
      (node (ref "Q58") (pin "E") (pinfunction "E_E") (pintype "passive"))
    )
    (net (code "26") (name "Net-(Q57-PadE)") (class "Default")
      (node (ref "Q57") (pin "E") (pinfunction "E_E") (pintype "passive"))
      (node (ref "Q62") (pin "C") (pinfunction "C_C") (pintype "passive"))
      (node (ref "R65") (pin "1") (pinfunction "1_1") (pintype "passive"))
    )
    (net (code "27") (name "Net-(Q58-PadC)") (class "Default")
      (node (ref "Q58") (pin "C") (pinfunction "C_C") (pintype "passive"))
      (node (ref "Q61") (pin "B") (pinfunction "B_B") (pintype "passive"))
      (node (ref "Q72") (pin "C") (pinfunction "C_C") (pintype "passive"))
    )
    (net (code "28") (name "Net-(Q59-B)") (class "Default")
      (node (ref "C17") (pin "1") (pinfunction "1_1") (pintype "passive"))
      (node (ref "C19") (pin "2") (pinfunction "2_2") (pintype "passive"))
      (node (ref "Q59") (pin "1") (pinfunction "B_1") (pintype "passive"))
      (node (ref "Q67") (pin "2") (pinfunction "C_2") (pintype "passive"))
      (node (ref "Q67") (pin "4") (pinfunction "C_4") (pintype "passive"))
      (node (ref "Q74") (pin "2") (pinfunction "C_2") (pintype "passive"))
      (node (ref "Q75") (pin "2") (pinfunction "C_2") (pintype "passive"))
      (node (ref "Q75") (pin "4") (pinfunction "C_4") (pintype "passive"))
      (node (ref "R76") (pin "1") (pinfunction "1_1") (pintype "passive"))
      (node (ref "R90") (pin "2") (pinfunction "2_2") (pintype "passive"))
    )
    (net (code "29") (name "Net-(Q59-E)") (class "Default")
      (node (ref "Q59") (pin "3") (pinfunction "E_3") (pintype "passive"))
      (node (ref "Q68") (pin "1") (pinfunction "B_1") (pintype "passive"))
      (node (ref "R79") (pin "2") (pinfunction "2_2") (pintype "passive"))
    )
    (net (code "30") (name "Net-(Q60-B)") (class "Default")
      (node (ref "C17") (pin "2") (pinfunction "2_2") (pintype "passive"))
      (node (ref "C20") (pin "1") (pinfunction "1_1") (pintype "passive"))
      (node (ref "Q60") (pin "1") (pinfunction "B_1") (pintype "passive"))
      (node (ref "Q74") (pin "3") (pinfunction "E_3") (pintype "passive"))
      (node (ref "Q77") (pin "2") (pinfunction "C_2") (pintype "passive"))
      (node (ref "Q77") (pin "4") (pinfunction "C_4") (pintype "passive"))
      (node (ref "Q79") (pin "2") (pinfunction "C_2") (pintype "passive"))
      (node (ref "Q79") (pin "4") (pinfunction "C_4") (pintype "passive"))
      (node (ref "R78") (pin "2") (pinfunction "2_2") (pintype "passive"))
      (node (ref "RV3") (pin "1") (pinfunction "A_1") (pintype "passive"))
      (node (ref "RV3") (pin "2") (pinfunction "S_2") (pintype "passive"))
    )
    (net (code "31") (name "Net-(Q60-E)") (class "Default")
      (node (ref "Q60") (pin "3") (pinfunction "E_3") (pintype "passive"))
      (node (ref "Q69") (pin "1") (pinfunction "B_1") (pintype "passive"))
      (node (ref "R79") (pin "1") (pinfunction "1_1") (pintype "passive"))
    )
    (net (code "32") (name "Net-(Q61-PadE)") (class "Default")
      (node (ref "Q61") (pin "E") (pinfunction "E_E") (pintype "passive"))
      (node (ref "Q72") (pin "B") (pinfunction "B_B") (pintype "passive"))
      (node (ref "Q73") (pin "B") (pinfunction "B_B") (pintype "passive"))
      (node (ref "Q73") (pin "C") (pinfunction "C_C") (pintype "passive"))
    )
    (net (code "33") (name "Net-(Q62-PadB)") (class "Default")
      (node (ref "Q62") (pin "B") (pinfunction "B_B") (pintype "passive"))
      (node (ref "Q64") (pin "B") (pinfunction "B_B") (pintype "passive"))
      (node (ref "R1") (pin "1") (pinfunction "1_1") (pintype "passive"))
      (node (ref "R80") (pin "2") (pinfunction "2_2") (pintype "passive"))
    )
    (net (code "34") (name "Net-(Q62-PadE)") (class "Default")
      (node (ref "Q62") (pin "E") (pinfunction "E_E") (pintype "passive"))
      (node (ref "R69") (pin "1") (pinfunction "1_1") (pintype "passive"))
    )
    (net (code "35") (name "Net-(Q63-PadE)") (class "Default")
      (node (ref "Q63") (pin "E") (pinfunction "E_E") (pintype "passive"))
      (node (ref "Q65") (pin "B") (pinfunction "B_B") (pintype "passive"))
      (node (ref "Q66") (pin "B") (pinfunction "B_B") (pintype "passive"))
      (node (ref "Q66") (pin "C") (pinfunction "C_C") (pintype "passive"))
    )
    (net (code "36") (name "Net-(Q64-PadE)") (class "Default")
      (node (ref "Q64") (pin "E") (pinfunction "E_E") (pintype "passive"))
      (node (ref "R70") (pin "2") (pinfunction "2_2") (pintype "passive"))
    )
    (net (code "37") (name "Net-(Q65-PadE)") (class "Default")
      (node (ref "Q65") (pin "E") (pinfunction "E_E") (pintype "passive"))
      (node (ref "R72") (pin "1") (pinfunction "1_1") (pintype "passive"))
    )
    (net (code "38") (name "Net-(Q67-E)") (class "Default")
      (node (ref "Q63") (pin "C") (pinfunction "C_C") (pintype "passive"))
      (node (ref "Q67") (pin "3") (pinfunction "E_3") (pintype "passive"))
    )
    (net (code "39") (name "Net-(Q72-PadE)") (class "Default")
      (node (ref "Q72") (pin "E") (pinfunction "E_E") (pintype "passive"))
      (node (ref "R74") (pin "2") (pinfunction "2_2") (pintype "passive"))
    )
    (net (code "40") (name "Net-(Q74-B)") (class "Default")
      (node (ref "Q74") (pin "1") (pinfunction "B_1") (pintype "passive"))
      (node (ref "R90") (pin "1") (pinfunction "1_1") (pintype "passive"))
      (node (ref "RV3") (pin "3") (pinfunction "E_3") (pintype "passive"))
    )
    (net (code "41") (name "Net-(Q75-B)") (class "Default")
      (node (ref "Q75") (pin "1") (pinfunction "B_1") (pintype "passive"))
      (node (ref "Q76") (pin "B") (pinfunction "B_B") (pintype "passive"))
      (node (ref "Q76") (pin "C") (pinfunction "C_C") (pintype "passive"))
      (node (ref "R82") (pin "2") (pinfunction "2_2") (pintype "passive"))
    )
    (net (code "42") (name "Net-(Q75-E)") (class "Default")
      (node (ref "Q75") (pin "3") (pinfunction "E_3") (pintype "passive"))
      (node (ref "R84") (pin "1") (pinfunction "1_1") (pintype "passive"))
    )
    (net (code "43") (name "Net-(Q76-PadE)") (class "Default")
      (node (ref "Q76") (pin "E") (pinfunction "E_E") (pintype "passive"))
      (node (ref "R85") (pin "1") (pinfunction "1_1") (pintype "passive"))
    )
    (net (code "44") (name "Net-(Q77-B)") (class "Default")
      (node (ref "Q77") (pin "1") (pinfunction "B_1") (pintype "passive"))
      (node (ref "Q78") (pin "B") (pinfunction "B_B") (pintype "passive"))
      (node (ref "Q78") (pin "C") (pinfunction "C_C") (pintype "passive"))
      (node (ref "R83") (pin "1") (pinfunction "1_1") (pintype "passive"))
    )
    (net (code "45") (name "Net-(Q77-E)") (class "Default")
      (node (ref "Q77") (pin "3") (pinfunction "E_3") (pintype "passive"))
      (node (ref "R86") (pin "2") (pinfunction "2_2") (pintype "passive"))
    )
    (net (code "46") (name "Net-(Q78-PadE)") (class "Default")
      (node (ref "Q78") (pin "E") (pinfunction "E_E") (pintype "passive"))
      (node (ref "R89") (pin "2") (pinfunction "2_2") (pintype "passive"))
    )
    (net (code "47") (name "Net-(Q79-B)") (class "Default")
      (node (ref "D20") (pin "A") (pinfunction "A_A") (pintype "passive"))
      (node (ref "Q79") (pin "1") (pinfunction "B_1") (pintype "passive"))
      (node (ref "R77") (pin "1") (pinfunction "1_1") (pintype "passive"))
    )
    (net (code "48") (name "Net-(Q79-E)") (class "Default")
      (node (ref "Q61") (pin "C") (pinfunction "C_C") (pintype "passive"))
      (node (ref "Q79") (pin "3") (pinfunction "E_3") (pintype "passive"))
    )
    (net (code "49") (name "Net-(Q80-PadE)") (class "Default")
      (node (ref "Q80") (pin "E") (pinfunction "E_E") (pintype "passive"))
      (node (ref "R63") (pin "1") (pinfunction "1_1") (pintype "passive"))
    )
    (net (code "50") (name "Net-(Q81-PadE)") (class "Default")
      (node (ref "Q81") (pin "E") (pinfunction "E_E") (pintype "passive"))
      (node (ref "R66") (pin "2") (pinfunction "2_2") (pintype "passive"))
    )
    (net (code "51") (name "Net-(R61-Pad1)") (class "Default")
      (node (ref "R61") (pin "1") (pinfunction "1_1") (pintype "passive"))
      (node (ref "R62") (pin "2") (pinfunction "2_2") (pintype "passive"))
      (node (ref "R64") (pin "1") (pinfunction "1_1") (pintype "passive"))
      (node (ref "R65") (pin "2") (pinfunction "2_2") (pintype "passive"))
    )
    (net (code "52") (name "Net-(X2B-KL)") (class "Default")
      (node (ref "R1") (pin "2") (pinfunction "2_2") (pintype "passive"))
      (node (ref "X2") (pin "2") (pinfunction "KL_2") (pintype "passive"))
    )
    (net (code "53") (name "Net-(X3A-KL)") (class "Default")
      (node (ref "R61") (pin "2") (pinfunction "2_2") (pintype "passive"))
      (node (ref "R68") (pin "1") (pinfunction "1_1") (pintype "passive"))
      (node (ref "R87") (pin "1") (pinfunction "1_1") (pintype "passive"))
      (node (ref "R88") (pin "2") (pinfunction "2_2") (pintype "passive"))
      (node (ref "X3") (pin "1") (pinfunction "KL_1") (pintype "passive"))
    )
    (net (code "54") (name "unconnected-(IC1-ON1-Pad1)") (class "Default")
      (node (ref "IC1") (pin "1") (pinfunction "ON1_1") (pintype "passive"))
    )
    (net (code "55") (name "unconnected-(IC1-ON2-Pad8)") (class "Default")
      (node (ref "IC1") (pin "8") (pinfunction "ON2_8") (pintype "passive"))
    )
    (net (code "56") (name "unconnected-(IC1-OPT-Pad5)") (class "Default")
      (node (ref "IC1") (pin "5") (pinfunction "OPT_5") (pintype "passive"))
    )
  )
)
